# MCU063A_EtherNET.net
KiCad netlist of a schematic drawn in Altium Designer
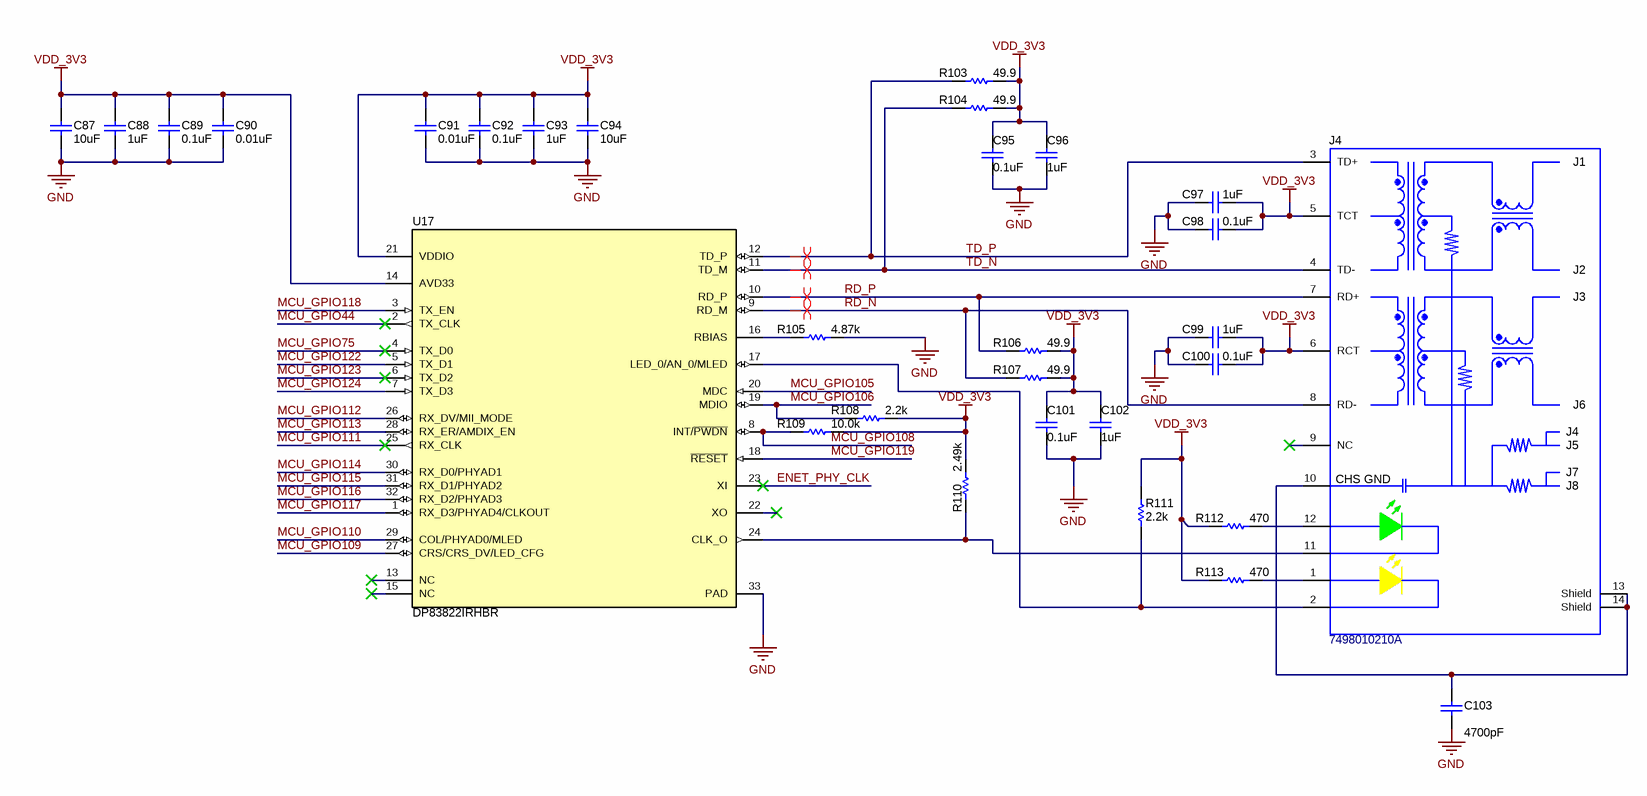
[diagram p0: MCU063A_EtherNET.SchDoc]

(export (version "E")
  (design (tool "Eeschema 10.0.6"))
  (components
    (comp (ref "C87")
      (value "CL05A106MQ5NUNC")
      (footprint "0402")
      (description "CAP, CERM, 10 uF, 6.3 V, +/- 20%, X5R, 0402")
      (fields
        (field (name "MANUFACTURER") "Samsung Electro-Mechanics")
        (field (name "VALUEDISPLAYED") "10uF")
        (field (name "PUBLISHER") "Texas Instruments")
      )
      (libsource (lib "Altium Vault - TI") (part "Capacitor"))
    )
    (comp (ref "C88")
      (value "EMK105BJ105KVHF")
      (footprint "0402")
      (description "CAP, CERM, 1 uF, 16 V, +/- 10%, X5R, 0402")
      (fields
        (field (name "MANUFACTURER") "Taiyo Yuden")
        (field (name "VALUEDISPLAYED") "1uF")
        (field (name "PUBLISHER") "Texas Instruments")
      )
      (libsource (lib "Altium Vault - TI") (part "Capacitor"))
    )
    (comp (ref "C89")
      (value "LMK105BJ104KV-F")
      (footprint "0402")
      (description "CAP, CERM, 0.1 uF, 10 V,+/- 10%, X5R, 0402")
      (fields
        (field (name "MANUFACTURER") "Taiyo Yuden")
        (field (name "VALUEDISPLAYED") "0.1uF")
        (field (name "PUBLISHER") "Texas Instruments")
      )
      (libsource (lib "Altium Vault - TI") (part "Capacitor"))
    )
    (comp (ref "C90")
      (value "885012205031")
      (footprint "0402")
      (description "CAP, CERM, 0.01 uF, 16 V, +/- 10%, X7R, 0402")
      (fields
        (field (name "MANUFACTURER") "Wurth Elektronik")
        (field (name "VALUEDISPLAYED") "0.01uF")
        (field (name "PUBLISHER") "Texas Instruments")
      )
      (libsource (lib "Altium Vault - TI") (part "Capacitor"))
    )
    (comp (ref "C91")
      (value "885012205031")
      (footprint "0402")
      (description "CAP, CERM, 0.01 uF, 16 V, +/- 10%, X7R, 0402")
      (fields
        (field (name "MANUFACTURER") "Wurth Elektronik")
        (field (name "VALUEDISPLAYED") "0.01uF")
        (field (name "PUBLISHER") "Texas Instruments")
      )
      (libsource (lib "Altium Vault - TI") (part "Capacitor"))
    )
    (comp (ref "C92")
      (value "LMK105BJ104KV-F")
      (footprint "0402")
      (description "CAP, CERM, 0.1 uF, 10 V,+/- 10%, X5R, 0402")
      (fields
        (field (name "MANUFACTURER") "Taiyo Yuden")
        (field (name "VALUEDISPLAYED") "0.1uF")
        (field (name "PUBLISHER") "Texas Instruments")
      )
      (libsource (lib "Altium Vault - TI") (part "Capacitor"))
    )
    (comp (ref "C93")
      (value "EMK105BJ105KVHF")
      (footprint "0402")
      (description "CAP, CERM, 1 uF, 16 V, +/- 10%, X5R, 0402")
      (fields
        (field (name "MANUFACTURER") "Taiyo Yuden")
        (field (name "VALUEDISPLAYED") "1uF")
        (field (name "PUBLISHER") "Texas Instruments")
      )
      (libsource (lib "Altium Vault - TI") (part "Capacitor"))
    )
    (comp (ref "C94")
      (value "CL05A106MQ5NUNC")
      (footprint "0402")
      (description "CAP, CERM, 10 uF, 6.3 V, +/- 20%, X5R, 0402")
      (fields
        (field (name "MANUFACTURER") "Samsung Electro-Mechanics")
        (field (name "VALUEDISPLAYED") "10uF")
        (field (name "PUBLISHER") "Texas Instruments")
      )
      (libsource (lib "Altium Vault - TI") (part "Capacitor"))
    )
    (comp (ref "C95")
      (value "LMK105BJ104KV-F")
      (footprint "0402")
      (description "CAP, CERM, 0.1 uF, 10 V,+/- 10%, X5R, 0402")
      (fields
        (field (name "MANUFACTURER") "Taiyo Yuden")
        (field (name "VALUEDISPLAYED") "0.1uF")
        (field (name "PUBLISHER") "Texas Instruments")
      )
      (libsource (lib "Altium Vault - TI") (part "Capacitor"))
    )
    (comp (ref "C96")
      (value "EMK105BJ105KVHF")
      (footprint "0402")
      (description "CAP, CERM, 1 uF, 16 V, +/- 10%, X5R, 0402")
      (fields
        (field (name "MANUFACTURER") "Taiyo Yuden")
        (field (name "VALUEDISPLAYED") "1uF")
        (field (name "PUBLISHER") "Texas Instruments")
      )
      (libsource (lib "Altium Vault - TI") (part "Capacitor"))
    )
    (comp (ref "C97")
      (value "EMK105BJ105KVHF")
      (footprint "0402")
      (description "CAP, CERM, 1 uF, 16 V, +/- 10%, X5R, 0402")
      (fields
        (field (name "MANUFACTURER") "Taiyo Yuden")
        (field (name "VALUEDISPLAYED") "1uF")
        (field (name "PUBLISHER") "Texas Instruments")
      )
      (libsource (lib "Altium Vault - TI") (part "Capacitor"))
    )
    (comp (ref "C98")
      (value "LMK105BJ104KV-F")
      (footprint "0402")
      (description "CAP, CERM, 0.1 uF, 10 V,+/- 10%, X5R, 0402")
      (fields
        (field (name "MANUFACTURER") "Taiyo Yuden")
        (field (name "VALUEDISPLAYED") "0.1uF")
        (field (name "PUBLISHER") "Texas Instruments")
      )
      (libsource (lib "Altium Vault - TI") (part "Capacitor"))
    )
    (comp (ref "C99")
      (value "EMK105BJ105KVHF")
      (footprint "0402")
      (description "CAP, CERM, 1 uF, 16 V, +/- 10%, X5R, 0402")
      (fields
        (field (name "MANUFACTURER") "Taiyo Yuden")
        (field (name "VALUEDISPLAYED") "1uF")
        (field (name "PUBLISHER") "Texas Instruments")
      )
      (libsource (lib "Altium Vault - TI") (part "Capacitor"))
    )
    (comp (ref "C100")
      (value "LMK105BJ104KV-F")
      (footprint "0402")
      (description "CAP, CERM, 0.1 uF, 10 V,+/- 10%, X5R, 0402")
      (fields
        (field (name "MANUFACTURER") "Taiyo Yuden")
        (field (name "VALUEDISPLAYED") "0.1uF")
        (field (name "PUBLISHER") "Texas Instruments")
      )
      (libsource (lib "Altium Vault - TI") (part "Capacitor"))
    )
    (comp (ref "C101")
      (value "LMK105BJ104KV-F")
      (footprint "0402")
      (description "CAP, CERM, 0.1 uF, 10 V,+/- 10%, X5R, 0402")
      (fields
        (field (name "MANUFACTURER") "Taiyo Yuden")
        (field (name "VALUEDISPLAYED") "0.1uF")
        (field (name "PUBLISHER") "Texas Instruments")
      )
      (libsource (lib "Altium Vault - TI") (part "Capacitor"))
    )
    (comp (ref "C102")
      (value "EMK105BJ105KVHF")
      (footprint "0402")
      (description "CAP, CERM, 1 uF, 16 V, +/- 10%, X5R, 0402")
      (fields
        (field (name "MANUFACTURER") "Taiyo Yuden")
        (field (name "VALUEDISPLAYED") "1uF")
        (field (name "PUBLISHER") "Texas Instruments")
      )
      (libsource (lib "Altium Vault - TI") (part "Capacitor"))
    )
    (comp (ref "C103")
      (value "12061C472KAT2A")
      (footprint "1206")
      (description "CAP, CERM, 4700 pF, 100 V, +/- 10%, X7R, 1206")
      (fields
        (field (name "MANUFACTURER") "AVX")
        (field (name "VALUEDISPLAYED") "4700pF")
        (field (name "PUBLISHER") "Texas Instruments")
      )
      (libsource (lib "Altium Vault - TI") (part "Capacitor"))
    )
    (comp (ref "J4")
      (value "7498010210A")
      (footprint "Wurth_7498010210A")
      (description "Connector, RJ45, 1x1, Gold, R/A, SMT")
      (fields (field (name "MANUFACTURER") "Wurth Elektronik"))
      (libsource (lib "Altium Vault - TI") (part "Wurth_7498010210A"))
    )
    (comp (ref "R103")
      (value "RC0402FR-0749R9L")
      (footprint "0402")
      (description "RES, 49.9, 1%, 0.063 W, 0402")
      (fields
        (field (name "MANUFACTURER") "Yageo America")
        (field (name "VALUEDISPLAYED") "49.9")
        (field (name "PUBLISHER") "Texas Instruments")
      )
      (libsource (lib "Altium Vault - TI") (part "Resistor"))
    )
    (comp (ref "R104")
      (value "RC0402FR-0749R9L")
      (footprint "0402")
      (description "RES, 49.9, 1%, 0.063 W, 0402")
      (fields
        (field (name "MANUFACTURER") "Yageo America")
        (field (name "VALUEDISPLAYED") "49.9")
        (field (name "PUBLISHER") "Texas Instruments")
      )
      (libsource (lib "Altium Vault - TI") (part "Resistor"))
    )
    (comp (ref "R105")
      (value "CRCW04024K87FKED")
      (footprint "0402")
      (description "RES, 4.87 k, 1%, 0.063 W, AEC-Q200 Grade 0, 0402")
      (fields (field (name "MANUFACTURER") "Vishay-Dale") (field (name "VALUEDISPLAYED") "4.87k"))
      (libsource (lib "Altium Vault - TI") (part "Resistor"))
    )
    (comp (ref "R106")
      (value "RC0402FR-0749R9L")
      (footprint "0402")
      (description "RES, 49.9, 1%, 0.063 W, 0402")
      (fields
        (field (name "MANUFACTURER") "Yageo America")
        (field (name "VALUEDISPLAYED") "49.9")
        (field (name "PUBLISHER") "Texas Instruments")
      )
      (libsource (lib "Altium Vault - TI") (part "Resistor"))
    )
    (comp (ref "R107")
      (value "RC0402FR-0749R9L")
      (footprint "0402")
      (description "RES, 49.9, 1%, 0.063 W, 0402")
      (fields
        (field (name "MANUFACTURER") "Yageo America")
        (field (name "VALUEDISPLAYED") "49.9")
        (field (name "PUBLISHER") "Texas Instruments")
      )
      (libsource (lib "Altium Vault - TI") (part "Resistor"))
    )
    (comp (ref "R108")
      (value "CRCW04022K20JNED")
      (footprint "0402")
      (description "RES, 2.2 k, 5%, 0.063 W, AEC-Q200 Grade 0, 0402")
      (fields (field (name "MANUFACTURER") "Vishay-Dale") (field (name "VALUEDISPLAYED") "2.2k"))
      (libsource (lib "Altium Vault - TI") (part "Resistor"))
    )
    (comp (ref "R109")
      (value "RC0402FR-0710KL")
      (footprint "0402")
      (description "RES, 10.0 k, 1%, 0.063 W, 0402")
      (fields (field (name "MANUFACTURER") "Yageo America") (field (name "VALUEDISPLAYED") "10.0k"))
      (libsource (lib "Altium Vault - TI") (part "Resistor"))
    )
    (comp (ref "R110")
      (value "CRCW04022K49FKED")
      (footprint "0402")
      (description "RES, 2.49 k, 1%, 0.063 W, AEC-Q200 Grade 0, 0402")
      (fields (field (name "MANUFACTURER") "Vishay-Dale") (field (name "VALUEDISPLAYED") "2.49k"))
      (libsource (lib "Altium Vault - TI") (part "Resistor"))
    )
    (comp (ref "R111")
      (value "CRCW04022K20JNED")
      (footprint "0402")
      (description "RES, 2.2 k, 5%, 0.063 W, AEC-Q200 Grade 0, 0402")
      (fields (field (name "MANUFACTURER") "Vishay-Dale") (field (name "VALUEDISPLAYED") "2.2k"))
      (libsource (lib "Altium Vault - TI") (part "Resistor"))
    )
    (comp (ref "R112")
      (value "CRCW0603470RJNEA")
      (footprint "0603")
      (description "RES, 470, 5%, 0.1 W, AEC-Q200 Grade 0, 0603")
      (fields (field (name "MANUFACTURER") "Vishay-Dale") (field (name "VALUEDISPLAYED") "470"))
      (libsource (lib "Altium Vault - TI") (part "Resistor"))
    )
    (comp (ref "R113")
      (value "CRCW0603470RJNEA")
      (footprint "0603")
      (description "RES, 470, 5%, 0.1 W, AEC-Q200 Grade 0, 0603")
      (fields (field (name "MANUFACTURER") "Vishay-Dale") (field (name "VALUEDISPLAYED") "470"))
      (libsource (lib "Altium Vault - TI") (part "Resistor"))
    )
    (comp (ref "U17")
      (value "DP83822IRHBR")
      (footprint "RHB0032B")
      (description "Robust, Low Power 10/100 Ethernet Physical Layer Transceiver, RHB0032B (VQFN-32)")
      (fields
        (field (name "ALTERNATE PARTNUMBER") "DP83822IRHBT")
        (field (name "PARTNUMBER") "DP83822IRHBR")
        (field (name "MANUFACTURER") "Texas Instruments")
      )
      (libsource (lib "Altium Vault - TI") (part "DP83822"))
    )
  )
  (nets
    (net (code "1") (name "/ENET_PHY_CLK") (class "Default")
      (node (ref "U17") (pin "23") (pinfunction "XI_23") (pintype "passive+no_connect"))
    )
    (net (code "2") (name "/MCU_GPIO44") (class "Default")
      (node (ref "U17") (pin "2") (pinfunction "TX_CLK_2") (pintype "output+no_connect"))
    )
    (net (code "3") (name "/MCU_GPIO75") (class "Default")
      (node (ref "U17") (pin "4") (pinfunction "TX_D0_4") (pintype "input+no_connect"))
    )
    (net (code "4") (name "/MCU_GPIO105") (class "Default")
      (node (ref "U17") (pin "20") (pinfunction "MDC_20") (pintype "input"))
    )
    (net (code "5") (name "/MCU_GPIO106") (class "Default")
      (node (ref "R108") (pin "2") (pinfunction "2_2") (pintype "passive"))
      (node (ref "U17") (pin "19") (pinfunction "MDIO_19") (pintype "bidirectional"))
    )
    (net (code "6") (name "/MCU_GPIO108") (class "Default")
      (node (ref "R109") (pin "1") (pinfunction "1_1") (pintype "passive"))
      (node (ref "U17") (pin "8") (pinfunction "INT/~{PWDN}_8") (pintype "bidirectional"))
    )
    (net (code "7") (name "/MCU_GPIO109") (class "Default")
      (node (ref "U17") (pin "27") (pinfunction "CRS/CRS_DV/LED_CFG_27") (pintype "bidirectional"))
    )
    (net (code "8") (name "/MCU_GPIO110") (class "Default")
      (node (ref "U17") (pin "29") (pinfunction "COL/PHYAD0/MLED_29") (pintype "bidirectional"))
    )
    (net (code "9") (name "/MCU_GPIO111") (class "Default")
      (node (ref "U17") (pin "25") (pinfunction "RX_CLK_25") (pintype "output+no_connect"))
    )
    (net (code "10") (name "/MCU_GPIO112") (class "Default")
      (node (ref "U17") (pin "26") (pinfunction "RX_DV/MII_MODE_26") (pintype "bidirectional"))
    )
    (net (code "11") (name "/MCU_GPIO113") (class "Default")
      (node (ref "U17") (pin "28") (pinfunction "RX_ER/AMDIX_EN_28") (pintype "bidirectional"))
    )
    (net (code "12") (name "/MCU_GPIO114") (class "Default")
      (node (ref "U17") (pin "30") (pinfunction "RX_D0/PHYAD1_30") (pintype "bidirectional"))
    )
    (net (code "13") (name "/MCU_GPIO115") (class "Default")
      (node (ref "U17") (pin "31") (pinfunction "RX_D1/PHYAD2_31") (pintype "bidirectional"))
    )
    (net (code "14") (name "/MCU_GPIO116") (class "Default")
      (node (ref "U17") (pin "32") (pinfunction "RX_D2/PHYAD3_32") (pintype "bidirectional"))
    )
    (net (code "15") (name "/MCU_GPIO117") (class "Default")
      (node (ref "U17") (pin "1") (pinfunction "RX_D3/PHYAD4/CLKOUT_1") (pintype "bidirectional"))
    )
    (net (code "16") (name "/MCU_GPIO118") (class "Default")
      (node (ref "U17") (pin "3") (pinfunction "TX_EN_3") (pintype "input"))
    )
    (net (code "17") (name "/MCU_GPIO119") (class "Default")
      (node (ref "U17") (pin "18") (pinfunction "RESET_18") (pintype "input"))
    )
    (net (code "18") (name "/MCU_GPIO122") (class "Default")
      (node (ref "U17") (pin "5") (pinfunction "TX_D1_5") (pintype "input"))
    )
    (net (code "19") (name "/MCU_GPIO123") (class "Default")
      (node (ref "U17") (pin "6") (pinfunction "TX_D2_6") (pintype "input+no_connect"))
    )
    (net (code "20") (name "/MCU_GPIO124") (class "Default")
      (node (ref "U17") (pin "7") (pinfunction "TX_D3_7") (pintype "input"))
    )
    (net (code "21") (name "/RD_N") (class "Default")
      (node (ref "J4") (pin "8") (pinfunction "RD-_8") (pintype "passive"))
      (node (ref "R107") (pin "1") (pinfunction "1_1") (pintype "passive"))
      (node (ref "U17") (pin "9") (pinfunction "RD_M_9") (pintype "bidirectional"))
    )
    (net (code "22") (name "/RD_P") (class "Default")
      (node (ref "J4") (pin "7") (pinfunction "RD+_7") (pintype "passive"))
      (node (ref "R106") (pin "1") (pinfunction "1_1") (pintype "passive"))
      (node (ref "U17") (pin "10") (pinfunction "RD_P_10") (pintype "bidirectional"))
    )
    (net (code "23") (name "/TD_N") (class "Default")
      (node (ref "J4") (pin "4") (pinfunction "TD-_4") (pintype "passive"))
      (node (ref "R104") (pin "1") (pinfunction "1_1") (pintype "passive"))
      (node (ref "U17") (pin "11") (pinfunction "TD_M_11") (pintype "bidirectional"))
    )
    (net (code "24") (name "/TD_P") (class "Default")
      (node (ref "J4") (pin "3") (pinfunction "TD+_3") (pintype "passive"))
      (node (ref "R103") (pin "1") (pinfunction "1_1") (pintype "passive"))
      (node (ref "U17") (pin "12") (pinfunction "TD_P_12") (pintype "bidirectional"))
    )
    (net (code "25") (name "GND") (class "Default")
      (node (ref "C100") (pin "1") (pinfunction "1_1") (pintype "passive"))
      (node (ref "C101") (pin "2") (pinfunction "2_2") (pintype "passive"))
      (node (ref "C102") (pin "2") (pinfunction "2_2") (pintype "passive"))
      (node (ref "C103") (pin "1") (pinfunction "1_1") (pintype "passive"))
      (node (ref "C87") (pin "2") (pinfunction "2_2") (pintype "passive"))
      (node (ref "C88") (pin "2") (pinfunction "2_2") (pintype "passive"))
      (node (ref "C89") (pin "2") (pinfunction "2_2") (pintype "passive"))
      (node (ref "C90") (pin "2") (pinfunction "2_2") (pintype "passive"))
      (node (ref "C91") (pin "2") (pinfunction "2_2") (pintype "passive"))
      (node (ref "C92") (pin "2") (pinfunction "2_2") (pintype "passive"))
      (node (ref "C93") (pin "2") (pinfunction "2_2") (pintype "passive"))
      (node (ref "C94") (pin "2") (pinfunction "2_2") (pintype "passive"))
      (node (ref "C95") (pin "2") (pinfunction "2_2") (pintype "passive"))
      (node (ref "C96") (pin "2") (pinfunction "2_2") (pintype "passive"))
      (node (ref "C97") (pin "1") (pinfunction "1_1") (pintype "passive"))
      (node (ref "C98") (pin "1") (pinfunction "1_1") (pintype "passive"))
      (node (ref "C99") (pin "1") (pinfunction "1_1") (pintype "passive"))
      (node (ref "R105") (pin "2") (pinfunction "2_2") (pintype "passive"))
      (node (ref "U17") (pin "33") (pinfunction "PAD_33") (pintype "power_in"))
    )
    (net (code "26") (name "Net-(J4-CHS_GND)") (class "Default")
      (node (ref "C103") (pin "2") (pinfunction "2_2") (pintype "passive"))
      (node (ref "J4") (pin "10") (pinfunction "CHS_GND_10") (pintype "power_in"))
      (node (ref "J4") (pin "13") (pinfunction "Shield_13") (pintype "passive"))
      (node (ref "J4") (pin "14") (pinfunction "Shield_14") (pintype "passive"))
    )
    (net (code "27") (name "Net-(J4-LEFT_LED_ANODE)") (class "Default")
      (node (ref "J4") (pin "12") (pinfunction "LEFT_LED_ANODE_12") (pintype "passive"))
      (node (ref "R112") (pin "2") (pinfunction "2_2") (pintype "passive"))
    )
    (net (code "28") (name "Net-(J4-LEFT_LED_CATHODE)") (class "Default")
      (node (ref "J4") (pin "11") (pinfunction "LEFT_LED_CATHODE_11") (pintype "passive"))
      (node (ref "R110") (pin "1") (pinfunction "1_1") (pintype "passive"))
      (node (ref "U17") (pin "24") (pinfunction "CLK_O_24") (pintype "output"))
    )
    (net (code "29") (name "Net-(J4-RIGHT_LED_ANODE)") (class "Default")
      (node (ref "J4") (pin "1") (pinfunction "RIGHT_LED_ANODE_1") (pintype "passive"))
      (node (ref "R113") (pin "2") (pinfunction "2_2") (pintype "passive"))
    )
    (net (code "30") (name "Net-(J4-RIGHT_LED_CATHODE)") (class "Default")
      (node (ref "J4") (pin "2") (pinfunction "RIGHT_LED_CATHODE_2") (pintype "passive"))
      (node (ref "R111") (pin "1") (pinfunction "1_1") (pintype "passive"))
      (node (ref "U17") (pin "17") (pinfunction "LED_0/AN_0/MLED_17") (pintype "bidirectional"))
    )
    (net (code "31") (name "Net-(U17-RBIAS)") (class "Default")
      (node (ref "R105") (pin "1") (pinfunction "1_1") (pintype "passive"))
      (node (ref "U17") (pin "16") (pinfunction "RBIAS_16") (pintype "passive"))
    )
    (net (code "32") (name "VDD_3V3") (class "Default")
      (node (ref "C100") (pin "2") (pinfunction "2_2") (pintype "passive"))
      (node (ref "C101") (pin "1") (pinfunction "1_1") (pintype "passive"))
      (node (ref "C102") (pin "1") (pinfunction "1_1") (pintype "passive"))
      (node (ref "C87") (pin "1") (pinfunction "1_1") (pintype "passive"))
      (node (ref "C88") (pin "1") (pinfunction "1_1") (pintype "passive"))
      (node (ref "C89") (pin "1") (pinfunction "1_1") (pintype "passive"))
      (node (ref "C90") (pin "1") (pinfunction "1_1") (pintype "passive"))
      (node (ref "C91") (pin "1") (pinfunction "1_1") (pintype "passive"))
      (node (ref "C92") (pin "1") (pinfunction "1_1") (pintype "passive"))
      (node (ref "C93") (pin "1") (pinfunction "1_1") (pintype "passive"))
      (node (ref "C94") (pin "1") (pinfunction "1_1") (pintype "passive"))
      (node (ref "C95") (pin "1") (pinfunction "1_1") (pintype "passive"))
      (node (ref "C96") (pin "1") (pinfunction "1_1") (pintype "passive"))
      (node (ref "C97") (pin "2") (pinfunction "2_2") (pintype "passive"))
      (node (ref "C98") (pin "2") (pinfunction "2_2") (pintype "passive"))
      (node (ref "C99") (pin "2") (pinfunction "2_2") (pintype "passive"))
      (node (ref "J4") (pin "5") (pinfunction "TCT_5") (pintype "passive"))
      (node (ref "J4") (pin "6") (pinfunction "RCT_6") (pintype "passive"))
      (node (ref "R103") (pin "2") (pinfunction "2_2") (pintype "passive"))
      (node (ref "R104") (pin "2") (pinfunction "2_2") (pintype "passive"))
      (node (ref "R106") (pin "2") (pinfunction "2_2") (pintype "passive"))
      (node (ref "R107") (pin "2") (pinfunction "2_2") (pintype "passive"))
      (node (ref "R108") (pin "1") (pinfunction "1_1") (pintype "passive"))
      (node (ref "R109") (pin "2") (pinfunction "2_2") (pintype "passive"))
      (node (ref "R110") (pin "2") (pinfunction "2_2") (pintype "passive"))
      (node (ref "R111") (pin "2") (pinfunction "2_2") (pintype "passive"))
      (node (ref "R112") (pin "1") (pinfunction "1_1") (pintype "passive"))
      (node (ref "R113") (pin "1") (pinfunction "1_1") (pintype "passive"))
      (node (ref "U17") (pin "14") (pinfunction "AVD33_14") (pintype "power_in"))
      (node (ref "U17") (pin "21") (pinfunction "VDDIO_21") (pintype "power_in"))
    )
    (net (code "33") (name "unconnected-(J4-NC-Pad9)") (class "Default")
      (node (ref "J4") (pin "9") (pinfunction "NC_9") (pintype "passive+no_connect"))
    )
    (net (code "34") (name "unconnected-(U17-NC-Pad13)") (class "Default")
      (node (ref "U17") (pin "13") (pinfunction "NC_13") (pintype "passive+no_connect"))
    )
    (net (code "35") (name "unconnected-(U17-NC-Pad15)") (class "Default")
      (node (ref "U17") (pin "15") (pinfunction "NC_15") (pintype "passive+no_connect"))
    )
    (net (code "36") (name "unconnected-(U17-XO-Pad22)") (class "Default")
      (node (ref "U17") (pin "22") (pinfunction "XO_22") (pintype "passive+no_connect"))
    )
  )
)
